# MainBoard.net
KiCad netlist of a schematic drawn in EAGLE
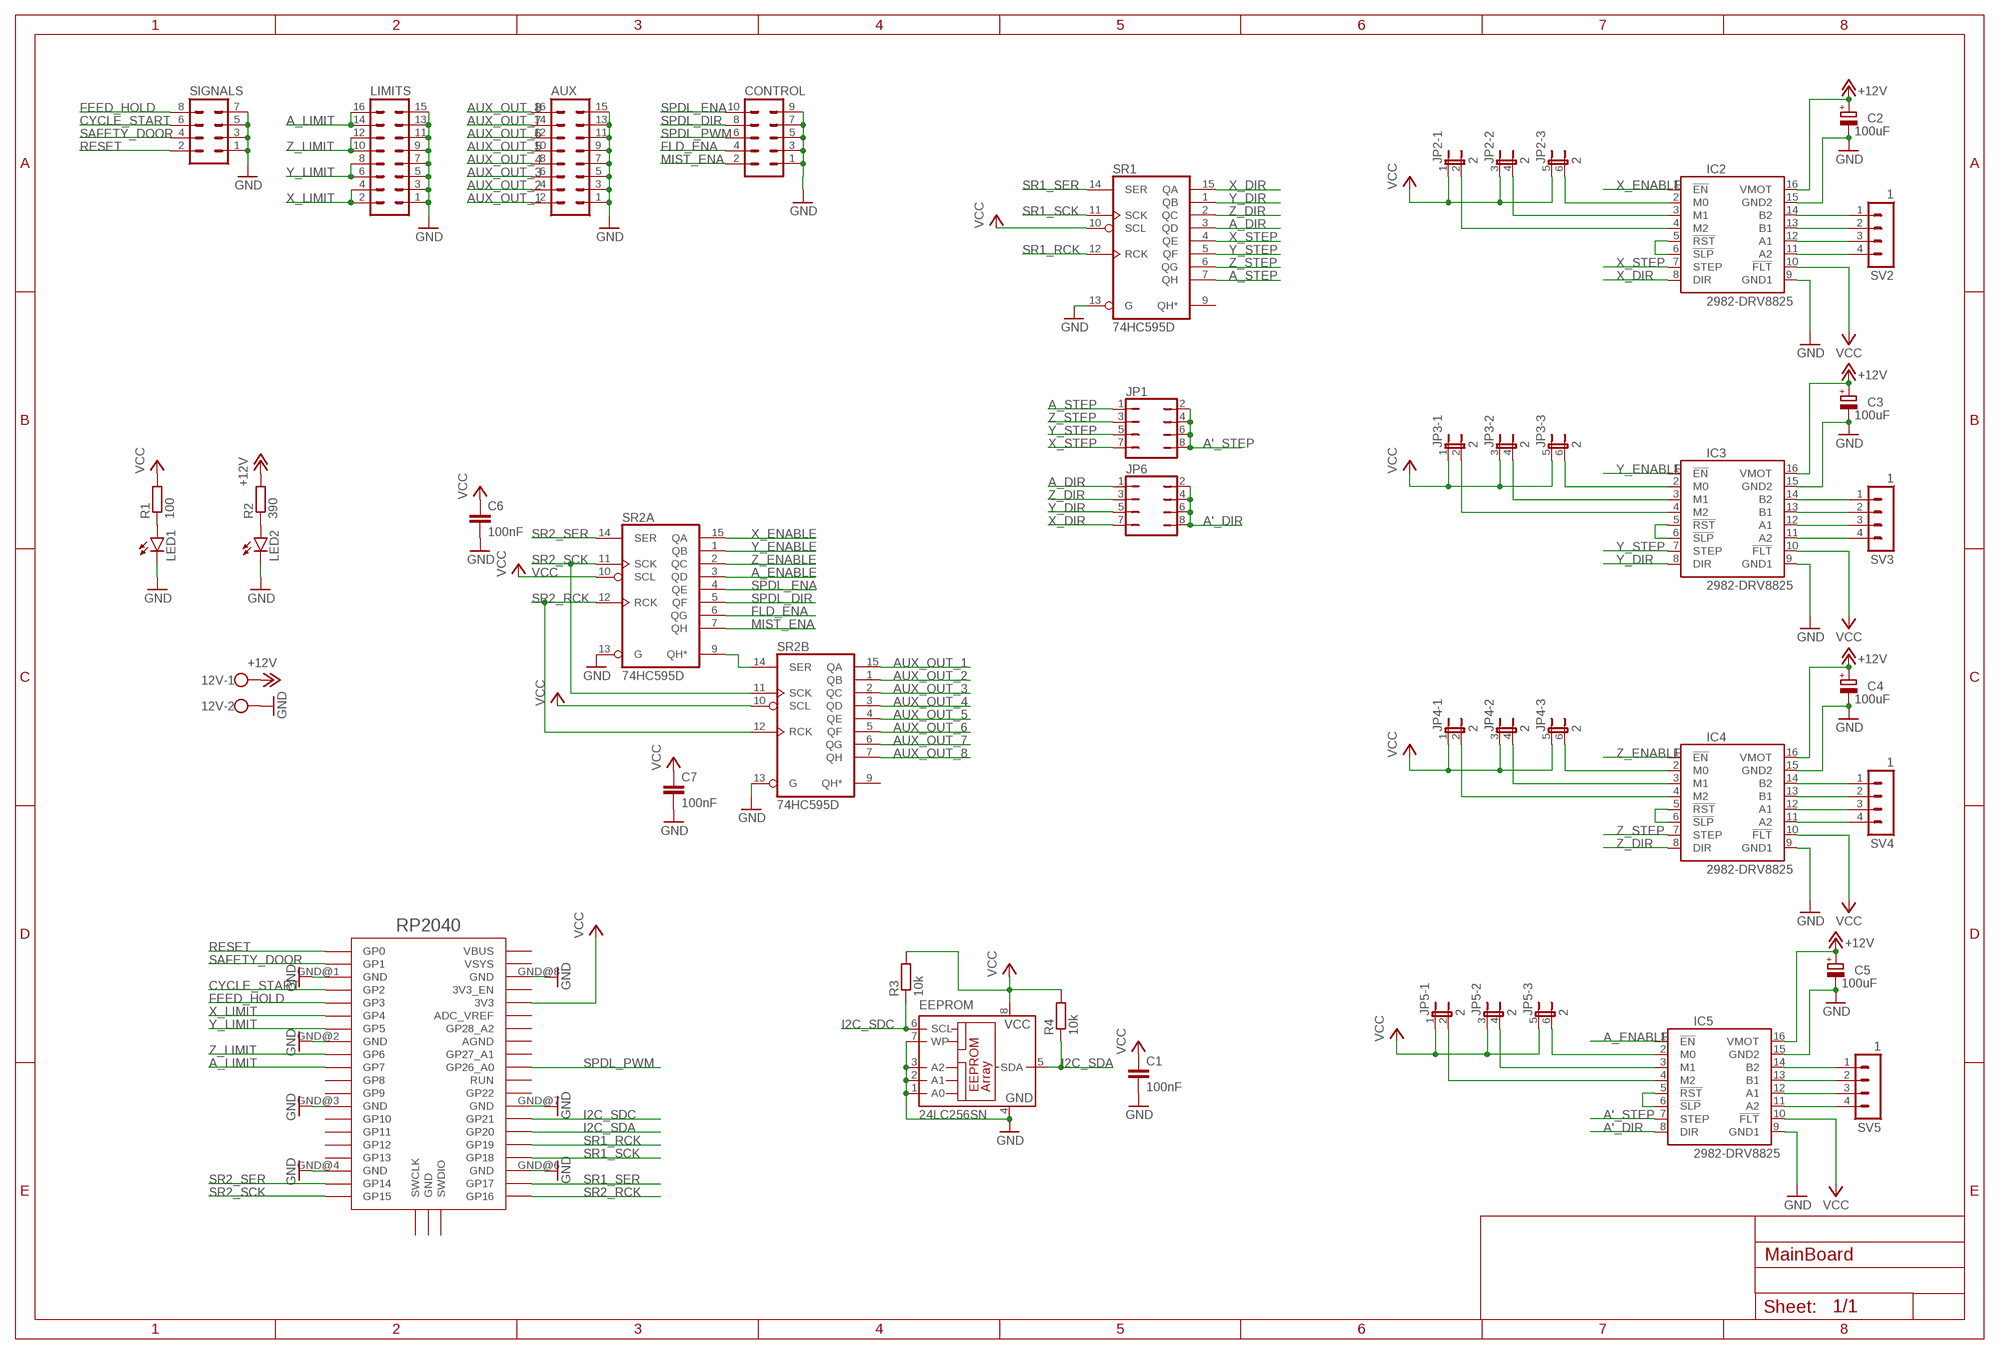
[diagram p0: schematic, sheet 1]

(export (version "E")
  (design (tool "Eeschema 10.0.6"))
  (components
    (comp (ref "12V")
      (value "W237-102")
      (footprint "eagle-import:W237-102")
      (fields (field (name "MPN") "237-102"))
      (libsource (lib "eagle-import") (part "W237-102"))
    )
    (comp (ref "AUX")
      (value "MA08-2")
      (footprint "eagle-import:MA08-2")
      (libsource (lib "eagle-import") (part "MA08-2"))
    )
    (comp (ref "C1")
      (value "100nF")
      (footprint "eagle-import:C0805")
      (libsource (lib "eagle-import") (part "C-EUC0805"))
    )
    (comp (ref "C2")
      (value "100uF")
      (footprint "eagle-import:E3,5-8")
      (libsource (lib "eagle-import") (part "CPOL-EUE3.5-8"))
    )
    (comp (ref "C3")
      (value "100uF")
      (footprint "eagle-import:E3,5-8")
      (libsource (lib "eagle-import") (part "CPOL-EUE3.5-8"))
    )
    (comp (ref "C4")
      (value "100uF")
      (footprint "eagle-import:E3,5-8")
      (libsource (lib "eagle-import") (part "CPOL-EUE3.5-8"))
    )
    (comp (ref "C5")
      (value "100uF")
      (footprint "eagle-import:E3,5-8")
      (libsource (lib "eagle-import") (part "CPOL-EUE3.5-8"))
    )
    (comp (ref "C6")
      (value "100nF")
      (footprint "eagle-import:C0805")
      (libsource (lib "eagle-import") (part "C-EUC0805"))
    )
    (comp (ref "C7")
      (value "100nF")
      (footprint "eagle-import:C0805")
      (libsource (lib "eagle-import") (part "C-EUC0805"))
    )
    (comp (ref "CONTROL")
      (value "MA05-2")
      (footprint "eagle-import:MA05-2")
      (libsource (lib "eagle-import") (part "MA05-2"))
    )
    (comp (ref "EEPROM")
      (value "24LC256SN")
      (footprint "eagle-import:SO-08")
      (fields (field (name "MF") "MICROCHIP") (field (name "MPN") "24LC256-I/SN"))
      (libsource (lib "eagle-import") (part "24SNLC256"))
    )
    (comp (ref "IC2")
      (value "2982-DRV8825")
      (footprint "eagle-import:DRV8825")
      (libsource (lib "eagle-import") (part "2982-DRV8825"))
    )
    (comp (ref "IC3")
      (value "2982-DRV8825")
      (footprint "eagle-import:DRV8825")
      (libsource (lib "eagle-import") (part "2982-DRV8825"))
    )
    (comp (ref "IC4")
      (value "2982-DRV8825")
      (footprint "eagle-import:DRV8825")
      (libsource (lib "eagle-import") (part "2982-DRV8825"))
    )
    (comp (ref "IC5")
      (value "2982-DRV8825")
      (footprint "eagle-import:DRV8825")
      (libsource (lib "eagle-import") (part "2982-DRV8825"))
    )
    (comp (ref "JP1")
      (value "JP4Q")
      (footprint "eagle-import:JP4Q")
      (libsource (lib "eagle-import") (part "JP4Q"))
    )
    (comp (ref "JP2")
      (value "2")
      (footprint "eagle-import:JP3Q")
      (libsource (lib "eagle-import") (part "JP3QE"))
    )
    (comp (ref "JP3")
      (value "2")
      (footprint "eagle-import:JP3Q")
      (libsource (lib "eagle-import") (part "JP3QE"))
    )
    (comp (ref "JP4")
      (value "2")
      (footprint "eagle-import:JP3Q")
      (libsource (lib "eagle-import") (part "JP3QE"))
    )
    (comp (ref "JP5")
      (value "2")
      (footprint "eagle-import:JP3Q")
      (libsource (lib "eagle-import") (part "JP3QE"))
    )
    (comp (ref "JP6")
      (value "JP4Q")
      (footprint "eagle-import:JP4Q")
      (libsource (lib "eagle-import") (part "JP4Q"))
    )
    (comp (ref "LED1")
      (value "LEDCHIP-LED0805")
      (footprint "eagle-import:CHIP-LED0805")
      (libsource (lib "eagle-import") (part "LEDCHIP-LED0805"))
    )
    (comp (ref "LED2")
      (value "LEDCHIP-LED0805")
      (footprint "eagle-import:CHIP-LED0805")
      (libsource (lib "eagle-import") (part "LEDCHIP-LED0805"))
    )
    (comp (ref "LIMITS")
      (value "MA08-2")
      (footprint "eagle-import:MA08-2")
      (libsource (lib "eagle-import") (part "MA08-2"))
    )
    (comp (ref "R1")
      (value "100")
      (footprint "eagle-import:R0805")
      (libsource (lib "eagle-import") (part "R-EU_R0805"))
    )
    (comp (ref "R2")
      (value "390")
      (footprint "eagle-import:R0805")
      (libsource (lib "eagle-import") (part "R-EU_R0805"))
    )
    (comp (ref "R3")
      (value "10k")
      (footprint "eagle-import:R0805")
      (libsource (lib "eagle-import") (part "R-EU_R0805"))
    )
    (comp (ref "R4")
      (value "10k")
      (footprint "eagle-import:R0805")
      (libsource (lib "eagle-import") (part "R-EU_R0805"))
    )
    (comp (ref "RP2040")
      (value "RPI_PICO_IG-TH")
      (footprint "eagle-import:RPI_PICO_TH")
      (libsource (lib "eagle-import") (part "RPI_PICO_IG-TH"))
    )
    (comp (ref "SIGNALS")
      (value "MA04-2")
      (footprint "eagle-import:MA04-2")
      (libsource (lib "eagle-import") (part "MA04-2"))
    )
    (comp (ref "SR1")
      (value "74HC595D")
      (footprint "eagle-import:SO16")
      (libsource (lib "eagle-import") (part "74595DHC"))
    )
    (comp (ref "SR2A")
      (value "74HC595D")
      (footprint "eagle-import:SO16")
      (libsource (lib "eagle-import") (part "74595DHC"))
    )
    (comp (ref "SR2B")
      (value "74HC595D")
      (footprint "eagle-import:SO16")
      (libsource (lib "eagle-import") (part "74595DHC"))
    )
    (comp (ref "SV2")
      (value "1")
      (footprint "eagle-import:MA04-1")
      (libsource (lib "eagle-import") (part "MA04-1"))
    )
    (comp (ref "SV3")
      (value "1")
      (footprint "eagle-import:MA04-1")
      (libsource (lib "eagle-import") (part "MA04-1"))
    )
    (comp (ref "SV4")
      (value "1")
      (footprint "eagle-import:MA04-1")
      (libsource (lib "eagle-import") (part "MA04-1"))
    )
    (comp (ref "SV5")
      (value "1")
      (footprint "eagle-import:MA04-1")
      (libsource (lib "eagle-import") (part "MA04-1"))
    )
  )
  (nets
    (net (code "1") (name "+12V") (class "Default")
      (node (ref "12V") (pin "1") (pinfunction "KL_1") (pintype "passive"))
      (node (ref "C2") (pin "+") (pinfunction "+_+") (pintype "passive"))
      (node (ref "C3") (pin "+") (pinfunction "+_+") (pintype "passive"))
      (node (ref "C4") (pin "+") (pinfunction "+_+") (pintype "passive"))
      (node (ref "C5") (pin "+") (pinfunction "+_+") (pintype "passive"))
      (node (ref "IC2") (pin "16") (pinfunction "VMOT_16") (pintype "power_in"))
      (node (ref "IC3") (pin "16") (pinfunction "VMOT_16") (pintype "power_in"))
      (node (ref "IC4") (pin "16") (pinfunction "VMOT_16") (pintype "power_in"))
      (node (ref "IC5") (pin "16") (pinfunction "VMOT_16") (pintype "power_in"))
      (node (ref "R2") (pin "2") (pinfunction "2_2") (pintype "passive"))
    )
    (net (code "2") (name "/A'_DIR") (class "Default")
      (node (ref "IC5") (pin "8") (pinfunction "DIR_8") (pintype "input"))
      (node (ref "JP6") (pin "2") (pinfunction "2_2") (pintype "passive"))
      (node (ref "JP6") (pin "4") (pinfunction "4_4") (pintype "passive"))
      (node (ref "JP6") (pin "6") (pinfunction "6_6") (pintype "passive"))
      (node (ref "JP6") (pin "8") (pinfunction "8_8") (pintype "passive"))
    )
    (net (code "3") (name "/A'_STEP") (class "Default")
      (node (ref "IC5") (pin "7") (pinfunction "STEP_7") (pintype "input"))
      (node (ref "JP1") (pin "2") (pinfunction "2_2") (pintype "passive"))
      (node (ref "JP1") (pin "4") (pinfunction "4_4") (pintype "passive"))
      (node (ref "JP1") (pin "6") (pinfunction "6_6") (pintype "passive"))
      (node (ref "JP1") (pin "8") (pinfunction "8_8") (pintype "passive"))
    )
    (net (code "4") (name "/AUX_OUT_1") (class "Default")
      (node (ref "AUX") (pin "2") (pinfunction "2_2") (pintype "passive"))
      (node (ref "SR2B") (pin "15") (pinfunction "QA_15") (pintype "tri_state"))
    )
    (net (code "5") (name "/AUX_OUT_2") (class "Default")
      (node (ref "AUX") (pin "4") (pinfunction "4_4") (pintype "passive"))
      (node (ref "SR2B") (pin "1") (pinfunction "QB_1") (pintype "tri_state"))
    )
    (net (code "6") (name "/AUX_OUT_3") (class "Default")
      (node (ref "AUX") (pin "6") (pinfunction "6_6") (pintype "passive"))
      (node (ref "SR2B") (pin "2") (pinfunction "QC_2") (pintype "tri_state"))
    )
    (net (code "7") (name "/AUX_OUT_4") (class "Default")
      (node (ref "AUX") (pin "8") (pinfunction "8_8") (pintype "passive"))
      (node (ref "SR2B") (pin "3") (pinfunction "QD_3") (pintype "tri_state"))
    )
    (net (code "8") (name "/AUX_OUT_5") (class "Default")
      (node (ref "AUX") (pin "10") (pinfunction "10_10") (pintype "passive"))
      (node (ref "SR2B") (pin "4") (pinfunction "QE_4") (pintype "tri_state"))
    )
    (net (code "9") (name "/AUX_OUT_6") (class "Default")
      (node (ref "AUX") (pin "12") (pinfunction "12_12") (pintype "passive"))
      (node (ref "SR2B") (pin "5") (pinfunction "QF_5") (pintype "tri_state"))
    )
    (net (code "10") (name "/AUX_OUT_7") (class "Default")
      (node (ref "AUX") (pin "14") (pinfunction "14_14") (pintype "passive"))
      (node (ref "SR2B") (pin "6") (pinfunction "QG_6") (pintype "tri_state"))
    )
    (net (code "11") (name "/AUX_OUT_8") (class "Default")
      (node (ref "AUX") (pin "16") (pinfunction "16_16") (pintype "passive"))
      (node (ref "SR2B") (pin "7") (pinfunction "QH_7") (pintype "tri_state"))
    )
    (net (code "12") (name "/A_DIR") (class "Default")
      (node (ref "JP6") (pin "1") (pinfunction "1_1") (pintype "passive"))
      (node (ref "SR1") (pin "3") (pinfunction "QD_3") (pintype "tri_state"))
    )
    (net (code "13") (name "/A_ENABLE") (class "Default")
      (node (ref "IC5") (pin "1") (pinfunction "~{EN}_1") (pintype "passive"))
      (node (ref "SR2A") (pin "3") (pinfunction "QD_3") (pintype "tri_state"))
    )
    (net (code "14") (name "/A_LIMIT") (class "Default")
      (node (ref "LIMITS") (pin "14") (pinfunction "14_14") (pintype "passive"))
      (node (ref "LIMITS") (pin "16") (pinfunction "16_16") (pintype "passive"))
      (node (ref "RP2040") (pin "GP7") (pinfunction "GP7_GP7") (pintype "bidirectional"))
    )
    (net (code "15") (name "/A_STEP") (class "Default")
      (node (ref "JP1") (pin "1") (pinfunction "1_1") (pintype "passive"))
      (node (ref "SR1") (pin "7") (pinfunction "QH_7") (pintype "tri_state"))
    )
    (net (code "16") (name "/CYCLE_START") (class "Default")
      (node (ref "RP2040") (pin "GP2") (pinfunction "GP2_GP2") (pintype "bidirectional"))
      (node (ref "SIGNALS") (pin "6") (pinfunction "6_6") (pintype "passive"))
    )
    (net (code "17") (name "/FEED_HOLD") (class "Default")
      (node (ref "RP2040") (pin "GP3") (pinfunction "GP3_GP3") (pintype "bidirectional"))
      (node (ref "SIGNALS") (pin "8") (pinfunction "8_8") (pintype "passive"))
    )
    (net (code "18") (name "/FLD_ENA") (class "Default")
      (node (ref "CONTROL") (pin "4") (pinfunction "4_4") (pintype "passive"))
      (node (ref "SR2A") (pin "6") (pinfunction "QG_6") (pintype "tri_state"))
    )
    (net (code "19") (name "/I2C_SDA") (class "Default")
      (node (ref "EEPROM") (pin "5") (pinfunction "SDA_5") (pintype "bidirectional"))
      (node (ref "R4") (pin "1") (pinfunction "1_1") (pintype "passive"))
      (node (ref "RP2040") (pin "GP20") (pinfunction "GP20_GP20") (pintype "bidirectional"))
    )
    (net (code "20") (name "/I2C_SDC") (class "Default")
      (node (ref "EEPROM") (pin "6") (pinfunction "SCL_6") (pintype "input"))
      (node (ref "R3") (pin "1") (pinfunction "1_1") (pintype "passive"))
      (node (ref "RP2040") (pin "GP21") (pinfunction "GP21_GP21") (pintype "bidirectional"))
    )
    (net (code "21") (name "/MIST_ENA") (class "Default")
      (node (ref "CONTROL") (pin "2") (pinfunction "2_2") (pintype "passive"))
      (node (ref "SR2A") (pin "7") (pinfunction "QH_7") (pintype "tri_state"))
    )
    (net (code "22") (name "/RESET") (class "Default")
      (node (ref "RP2040") (pin "GP0") (pinfunction "GP0_GP0") (pintype "bidirectional"))
      (node (ref "SIGNALS") (pin "2") (pinfunction "2_2") (pintype "passive"))
    )
    (net (code "23") (name "/SAFETY_DOOR") (class "Default")
      (node (ref "RP2040") (pin "GP1") (pinfunction "GP1_GP1") (pintype "bidirectional"))
      (node (ref "SIGNALS") (pin "4") (pinfunction "4_4") (pintype "passive"))
    )
    (net (code "24") (name "/SPDL_DIR") (class "Default")
      (node (ref "CONTROL") (pin "8") (pinfunction "8_8") (pintype "passive"))
      (node (ref "SR2A") (pin "5") (pinfunction "QF_5") (pintype "tri_state"))
    )
    (net (code "25") (name "/SPDL_ENA") (class "Default")
      (node (ref "CONTROL") (pin "10") (pinfunction "10_10") (pintype "passive"))
      (node (ref "SR2A") (pin "4") (pinfunction "QE_4") (pintype "tri_state"))
    )
    (net (code "26") (name "/SPDL_PWM") (class "Default")
      (node (ref "CONTROL") (pin "6") (pinfunction "6_6") (pintype "passive"))
      (node (ref "RP2040") (pin "GP26_A0") (pinfunction "GP26_A0_GP26_A0") (pintype "bidirectional"))
    )
    (net (code "27") (name "/SR1_RCK") (class "Default")
      (node (ref "RP2040") (pin "GP19") (pinfunction "GP19_GP19") (pintype "bidirectional"))
      (node (ref "SR1") (pin "12") (pinfunction "RCK_12") (pintype "input"))
    )
    (net (code "28") (name "/SR1_SCK") (class "Default")
      (node (ref "RP2040") (pin "GP18") (pinfunction "GP18_GP18") (pintype "bidirectional"))
      (node (ref "SR1") (pin "11") (pinfunction "SCK_11") (pintype "input"))
    )
    (net (code "29") (name "/SR1_SER") (class "Default")
      (node (ref "RP2040") (pin "GP17") (pinfunction "GP17_GP17") (pintype "bidirectional"))
      (node (ref "SR1") (pin "14") (pinfunction "SER_14") (pintype "input"))
    )
    (net (code "30") (name "/SR2_RCK") (class "Default")
      (node (ref "RP2040") (pin "GP16") (pinfunction "GP16_GP16") (pintype "bidirectional"))
      (node (ref "SR2A") (pin "12") (pinfunction "RCK_12") (pintype "input"))
      (node (ref "SR2B") (pin "12") (pinfunction "RCK_12") (pintype "input"))
    )
    (net (code "31") (name "/SR2_SCK") (class "Default")
      (node (ref "RP2040") (pin "GP15") (pinfunction "GP15_GP15") (pintype "bidirectional"))
      (node (ref "SR2A") (pin "11") (pinfunction "SCK_11") (pintype "input"))
      (node (ref "SR2B") (pin "11") (pinfunction "SCK_11") (pintype "input"))
    )
    (net (code "32") (name "/SR2_SER") (class "Default")
      (node (ref "RP2040") (pin "GP14") (pinfunction "GP14_GP14") (pintype "bidirectional"))
      (node (ref "SR2A") (pin "14") (pinfunction "SER_14") (pintype "input"))
    )
    (net (code "33") (name "/X_DIR") (class "Default")
      (node (ref "IC2") (pin "8") (pinfunction "DIR_8") (pintype "input"))
      (node (ref "JP6") (pin "7") (pinfunction "7_7") (pintype "passive"))
      (node (ref "SR1") (pin "15") (pinfunction "QA_15") (pintype "tri_state"))
    )
    (net (code "34") (name "/X_ENABLE") (class "Default")
      (node (ref "IC2") (pin "1") (pinfunction "~{EN}_1") (pintype "passive"))
      (node (ref "SR2A") (pin "15") (pinfunction "QA_15") (pintype "tri_state"))
    )
    (net (code "35") (name "/X_LIMIT") (class "Default")
      (node (ref "LIMITS") (pin "2") (pinfunction "2_2") (pintype "passive"))
      (node (ref "LIMITS") (pin "4") (pinfunction "4_4") (pintype "passive"))
      (node (ref "RP2040") (pin "GP4") (pinfunction "GP4_GP4") (pintype "bidirectional"))
    )
    (net (code "36") (name "/X_STEP") (class "Default")
      (node (ref "IC2") (pin "7") (pinfunction "STEP_7") (pintype "input"))
      (node (ref "JP1") (pin "7") (pinfunction "7_7") (pintype "passive"))
      (node (ref "SR1") (pin "4") (pinfunction "QE_4") (pintype "tri_state"))
    )
    (net (code "37") (name "/Y_DIR") (class "Default")
      (node (ref "IC3") (pin "8") (pinfunction "DIR_8") (pintype "input"))
      (node (ref "JP6") (pin "5") (pinfunction "5_5") (pintype "passive"))
      (node (ref "SR1") (pin "1") (pinfunction "QB_1") (pintype "tri_state"))
    )
    (net (code "38") (name "/Y_ENABLE") (class "Default")
      (node (ref "IC3") (pin "1") (pinfunction "~{EN}_1") (pintype "passive"))
      (node (ref "SR2A") (pin "1") (pinfunction "QB_1") (pintype "tri_state"))
    )
    (net (code "39") (name "/Y_LIMIT") (class "Default")
      (node (ref "LIMITS") (pin "6") (pinfunction "6_6") (pintype "passive"))
      (node (ref "LIMITS") (pin "8") (pinfunction "8_8") (pintype "passive"))
      (node (ref "RP2040") (pin "GP5") (pinfunction "GP5_GP5") (pintype "bidirectional"))
    )
    (net (code "40") (name "/Y_STEP") (class "Default")
      (node (ref "IC3") (pin "7") (pinfunction "STEP_7") (pintype "input"))
      (node (ref "JP1") (pin "5") (pinfunction "5_5") (pintype "passive"))
      (node (ref "SR1") (pin "5") (pinfunction "QF_5") (pintype "tri_state"))
    )
    (net (code "41") (name "/Z_DIR") (class "Default")
      (node (ref "IC4") (pin "8") (pinfunction "DIR_8") (pintype "input"))
      (node (ref "JP6") (pin "3") (pinfunction "3_3") (pintype "passive"))
      (node (ref "SR1") (pin "2") (pinfunction "QC_2") (pintype "tri_state"))
    )
    (net (code "42") (name "/Z_ENABLE") (class "Default")
      (node (ref "IC4") (pin "1") (pinfunction "~{EN}_1") (pintype "passive"))
      (node (ref "SR2A") (pin "2") (pinfunction "QC_2") (pintype "tri_state"))
    )
    (net (code "43") (name "/Z_LIMIT") (class "Default")
      (node (ref "LIMITS") (pin "10") (pinfunction "10_10") (pintype "passive"))
      (node (ref "LIMITS") (pin "12") (pinfunction "12_12") (pintype "passive"))
      (node (ref "RP2040") (pin "GP6") (pinfunction "GP6_GP6") (pintype "bidirectional"))
    )
    (net (code "44") (name "/Z_STEP") (class "Default")
      (node (ref "IC4") (pin "7") (pinfunction "STEP_7") (pintype "input"))
      (node (ref "JP1") (pin "3") (pinfunction "3_3") (pintype "passive"))
      (node (ref "SR1") (pin "6") (pinfunction "QG_6") (pintype "tri_state"))
    )
    (net (code "45") (name "GND") (class "Default")
      (node (ref "12V") (pin "2") (pinfunction "KL_2") (pintype "passive"))
      (node (ref "AUX") (pin "1") (pinfunction "1_1") (pintype "passive"))
      (node (ref "AUX") (pin "11") (pinfunction "11_11") (pintype "passive"))
      (node (ref "AUX") (pin "13") (pinfunction "13_13") (pintype "passive"))
      (node (ref "AUX") (pin "15") (pinfunction "15_15") (pintype "passive"))
      (node (ref "AUX") (pin "3") (pinfunction "3_3") (pintype "passive"))
      (node (ref "AUX") (pin "5") (pinfunction "5_5") (pintype "passive"))
      (node (ref "AUX") (pin "7") (pinfunction "7_7") (pintype "passive"))
      (node (ref "AUX") (pin "9") (pinfunction "9_9") (pintype "passive"))
      (node (ref "C1") (pin "2") (pinfunction "2_2") (pintype "passive"))
      (node (ref "C2") (pin "-") (pinfunction "-_-") (pintype "passive"))
      (node (ref "C3") (pin "-") (pinfunction "-_-") (pintype "passive"))
      (node (ref "C4") (pin "-") (pinfunction "-_-") (pintype "passive"))
      (node (ref "C5") (pin "-") (pinfunction "-_-") (pintype "passive"))
      (node (ref "C6") (pin "2") (pinfunction "2_2") (pintype "passive"))
      (node (ref "C7") (pin "2") (pinfunction "2_2") (pintype "passive"))
      (node (ref "CONTROL") (pin "1") (pinfunction "1_1") (pintype "passive"))
      (node (ref "CONTROL") (pin "3") (pinfunction "3_3") (pintype "passive"))
      (node (ref "CONTROL") (pin "5") (pinfunction "5_5") (pintype "passive"))
      (node (ref "CONTROL") (pin "7") (pinfunction "7_7") (pintype "passive"))
      (node (ref "CONTROL") (pin "9") (pinfunction "9_9") (pintype "passive"))
      (node (ref "EEPROM") (pin "1") (pinfunction "A0_1") (pintype "input"))
      (node (ref "EEPROM") (pin "2") (pinfunction "A1_2") (pintype "input"))
      (node (ref "EEPROM") (pin "3") (pinfunction "A2_3") (pintype "input"))
      (node (ref "EEPROM") (pin "4") (pinfunction "GND_4") (pintype "power_in"))
      (node (ref "EEPROM") (pin "7") (pinfunction "WP_7") (pintype "input"))
      (node (ref "IC2") (pin "15") (pinfunction "GND2_15") (pintype "power_in"))
      (node (ref "IC2") (pin "9") (pinfunction "GND1_9") (pintype "power_in"))
      (node (ref "IC3") (pin "15") (pinfunction "GND2_15") (pintype "power_in"))
      (node (ref "IC3") (pin "9") (pinfunction "GND1_9") (pintype "power_in"))
      (node (ref "IC4") (pin "15") (pinfunction "GND2_15") (pintype "power_in"))
      (node (ref "IC4") (pin "9") (pinfunction "GND1_9") (pintype "power_in"))
      (node (ref "IC5") (pin "15") (pinfunction "GND2_15") (pintype "power_in"))
      (node (ref "IC5") (pin "9") (pinfunction "GND1_9") (pintype "power_in"))
      (node (ref "LED1") (pin "C") (pinfunction "C_C") (pintype "passive"))
      (node (ref "LED2") (pin "C") (pinfunction "C_C") (pintype "passive"))
      (node (ref "LIMITS") (pin "1") (pinfunction "1_1") (pintype "passive"))
      (node (ref "LIMITS") (pin "11") (pinfunction "11_11") (pintype "passive"))
      (node (ref "LIMITS") (pin "13") (pinfunction "13_13") (pintype "passive"))
      (node (ref "LIMITS") (pin "15") (pinfunction "15_15") (pintype "passive"))
      (node (ref "LIMITS") (pin "3") (pinfunction "3_3") (pintype "passive"))
      (node (ref "LIMITS") (pin "5") (pinfunction "5_5") (pintype "passive"))
      (node (ref "LIMITS") (pin "7") (pinfunction "7_7") (pintype "passive"))
      (node (ref "LIMITS") (pin "9") (pinfunction "9_9") (pintype "passive"))
      (node (ref "RP2040") (pin "GND@1") (pinfunction "GND_GND@1") (pintype "bidirectional"))
      (node (ref "RP2040") (pin "GND@2") (pinfunction "GND_GND@2") (pintype "bidirectional"))
      (node (ref "RP2040") (pin "GND@3") (pinfunction "GND_GND@3") (pintype "bidirectional"))
      (node (ref "RP2040") (pin "GND@4") (pinfunction "GND_GND@4") (pintype "bidirectional"))
      (node (ref "RP2040") (pin "GND@6") (pinfunction "GND_GND@6") (pintype "bidirectional"))
      (node (ref "RP2040") (pin "GND@7") (pinfunction "GND_GND@7") (pintype "bidirectional"))
      (node (ref "RP2040") (pin "GND@8") (pinfunction "GND_GND@8") (pintype "bidirectional"))
      (node (ref "SIGNALS") (pin "1") (pinfunction "1_1") (pintype "passive"))
      (node (ref "SIGNALS") (pin "3") (pinfunction "3_3") (pintype "passive"))
      (node (ref "SIGNALS") (pin "5") (pinfunction "5_5") (pintype "passive"))
      (node (ref "SIGNALS") (pin "7") (pinfunction "7_7") (pintype "passive"))
      (node (ref "SR1") (pin "13") (pinfunction "G_13") (pintype "input"))
      (node (ref "SR2A") (pin "13") (pinfunction "G_13") (pintype "input"))
      (node (ref "SR2B") (pin "13") (pinfunction "G_13") (pintype "input"))
    )
    (net (code "46") (name "Net-(IC2-A1)") (class "Default")
      (node (ref "IC2") (pin "12") (pinfunction "A1_12") (pintype "output"))
      (node (ref "SV2") (pin "3") (pinfunction "3_3") (pintype "passive"))
    )
    (net (code "47") (name "Net-(IC2-A2)") (class "Default")
      (node (ref "IC2") (pin "11") (pinfunction "A2_11") (pintype "output"))
      (node (ref "SV2") (pin "4") (pinfunction "4_4") (pintype "passive"))
    )
    (net (code "48") (name "Net-(IC2-B1)") (class "Default")
      (node (ref "IC2") (pin "13") (pinfunction "B1_13") (pintype "output"))
      (node (ref "SV2") (pin "2") (pinfunction "2_2") (pintype "passive"))
    )
    (net (code "49") (name "Net-(IC2-B2)") (class "Default")
      (node (ref "IC2") (pin "14") (pinfunction "B2_14") (pintype "output"))
      (node (ref "SV2") (pin "1") (pinfunction "1_1") (pintype "passive"))
    )
    (net (code "50") (name "Net-(IC2-M0)") (class "Default")
      (node (ref "IC2") (pin "2") (pinfunction "M0_2") (pintype "passive"))
      (node (ref "JP2") (pin "6") (pinfunction "2_6") (pintype "passive"))
    )
    (net (code "51") (name "Net-(IC2-M1)") (class "Default")
      (node (ref "IC2") (pin "3") (pinfunction "M1_3") (pintype "passive"))
      (node (ref "JP2") (pin "4") (pinfunction "2_4") (pintype "passive"))
    )
    (net (code "52") (name "Net-(IC2-M2)") (class "Default")
      (node (ref "IC2") (pin "4") (pinfunction "M2_4") (pintype "passive"))
      (node (ref "JP2") (pin "2") (pinfunction "2_2") (pintype "passive"))
    )
    (net (code "53") (name "Net-(IC2-~{RST})") (class "Default")
      (node (ref "IC2") (pin "5") (pinfunction "~{RST}_5") (pintype "input"))
      (node (ref "IC2") (pin "6") (pinfunction "~{SLP}_6") (pintype "input"))
    )
    (net (code "54") (name "Net-(IC3-A1)") (class "Default")
      (node (ref "IC3") (pin "12") (pinfunction "A1_12") (pintype "output"))
      (node (ref "SV3") (pin "3") (pinfunction "3_3") (pintype "passive"))
    )
    (net (code "55") (name "Net-(IC3-A2)") (class "Default")
      (node (ref "IC3") (pin "11") (pinfunction "A2_11") (pintype "output"))
      (node (ref "SV3") (pin "4") (pinfunction "4_4") (pintype "passive"))
    )
    (net (code "56") (name "Net-(IC3-B1)") (class "Default")
      (node (ref "IC3") (pin "13") (pinfunction "B1_13") (pintype "output"))
      (node (ref "SV3") (pin "2") (pinfunction "2_2") (pintype "passive"))
    )
    (net (code "57") (name "Net-(IC3-B2)") (class "Default")
      (node (ref "IC3") (pin "14") (pinfunction "B2_14") (pintype "output"))
      (node (ref "SV3") (pin "1") (pinfunction "1_1") (pintype "passive"))
    )
    (net (code "58") (name "Net-(IC3-M0)") (class "Default")
      (node (ref "IC3") (pin "2") (pinfunction "M0_2") (pintype "passive"))
      (node (ref "JP3") (pin "6") (pinfunction "2_6") (pintype "passive"))
    )
    (net (code "59") (name "Net-(IC3-M1)") (class "Default")
      (node (ref "IC3") (pin "3") (pinfunction "M1_3") (pintype "passive"))
      (node (ref "JP3") (pin "4") (pinfunction "2_4") (pintype "passive"))
    )
    (net (code "60") (name "Net-(IC3-M2)") (class "Default")
      (node (ref "IC3") (pin "4") (pinfunction "M2_4") (pintype "passive"))
      (node (ref "JP3") (pin "2") (pinfunction "2_2") (pintype "passive"))
    )
    (net (code "61") (name "Net-(IC3-~{RST})") (class "Default")
      (node (ref "IC3") (pin "5") (pinfunction "~{RST}_5") (pintype "input"))
      (node (ref "IC3") (pin "6") (pinfunction "~{SLP}_6") (pintype "input"))
    )
    (net (code "62") (name "Net-(IC4-A1)") (class "Default")
      (node (ref "IC4") (pin "12") (pinfunction "A1_12") (pintype "output"))
      (node (ref "SV4") (pin "3") (pinfunction "3_3") (pintype "passive"))
    )
    (net (code "63") (name "Net-(IC4-A2)") (class "Default")
      (node (ref "IC4") (pin "11") (pinfunction "A2_11") (pintype "output"))
      (node (ref "SV4") (pin "4") (pinfunction "4_4") (pintype "passive"))
    )
    (net (code "64") (name "Net-(IC4-B1)") (class "Default")
      (node (ref "IC4") (pin "13") (pinfunction "B1_13") (pintype "output"))
      (node (ref "SV4") (pin "2") (pinfunction "2_2") (pintype "passive"))
    )
    (net (code "65") (name "Net-(IC4-B2)") (class "Default")
      (node (ref "IC4") (pin "14") (pinfunction "B2_14") (pintype "output"))
      (node (ref "SV4") (pin "1") (pinfunction "1_1") (pintype "passive"))
    )
    (net (code "66") (name "Net-(IC4-M0)") (class "Default")
      (node (ref "IC4") (pin "2") (pinfunction "M0_2") (pintype "passive"))
      (node (ref "JP4") (pin "6") (pinfunction "2_6") (pintype "passive"))
    )
    (net (code "67") (name "Net-(IC4-M1)") (class "Default")
      (node (ref "IC4") (pin "3") (pinfunction "M1_3") (pintype "passive"))
      (node (ref "JP4") (pin "4") (pinfunction "2_4") (pintype "passive"))
    )
    (net (code "68") (name "Net-(IC4-M2)") (class "Default")
      (node (ref "IC4") (pin "4") (pinfunction "M2_4") (pintype "passive"))
      (node (ref "JP4") (pin "2") (pinfunction "2_2") (pintype "passive"))
    )
    (net (code "69") (name "Net-(IC4-~{RST})") (class "Default")
      (node (ref "IC4") (pin "5") (pinfunction "~{RST}_5") (pintype "input"))
      (node (ref "IC4") (pin "6") (pinfunction "~{SLP}_6") (pintype "input"))
    )
    (net (code "70") (name "Net-(IC5-A1)") (class "Default")
      (node (ref "IC5") (pin "12") (pinfunction "A1_12") (pintype "output"))
      (node (ref "SV5") (pin "3") (pinfunction "3_3") (pintype "passive"))
    )
    (net (code "71") (name "Net-(IC5-A2)") (class "Default")
      (node (ref "IC5") (pin "11") (pinfunction "A2_11") (pintype "output"))
      (node (ref "SV5") (pin "4") (pinfunction "4_4") (pintype "passive"))
    )
    (net (code "72") (name "Net-(IC5-B1)") (class "Default")
      (node (ref "IC5") (pin "13") (pinfunction "B1_13") (pintype "output"))
      (node (ref "SV5") (pin "2") (pinfunction "2_2") (pintype "passive"))
    )
    (net (code "73") (name "Net-(IC5-B2)") (class "Default")
      (node (ref "IC5") (pin "14") (pinfunction "B2_14") (pintype "output"))
      (node (ref "SV5") (pin "1") (pinfunction "1_1") (pintype "passive"))
    )
    (net (code "74") (name "Net-(IC5-M0)") (class "Default")
      (node (ref "IC5") (pin "2") (pinfunction "M0_2") (pintype "passive"))
      (node (ref "JP5") (pin "6") (pinfunction "2_6") (pintype "passive"))
    )
    (net (code "75") (name "Net-(IC5-M1)") (class "Default")
      (node (ref "IC5") (pin "3") (pinfunction "M1_3") (pintype "passive"))
      (node (ref "JP5") (pin "4") (pinfunction "2_4") (pintype "passive"))
    )
    (net (code "76") (name "Net-(IC5-M2)") (class "Default")
      (node (ref "IC5") (pin "4") (pinfunction "M2_4") (pintype "passive"))
      (node (ref "JP5") (pin "2") (pinfunction "2_2") (pintype "passive"))
    )
    (net (code "77") (name "Net-(IC5-~{RST})") (class "Default")
      (node (ref "IC5") (pin "5") (pinfunction "~{RST}_5") (pintype "input"))
      (node (ref "IC5") (pin "6") (pinfunction "~{SLP}_6") (pintype "input"))
    )
    (net (code "78") (name "Net-(LED1-PadA)") (class "Default")
      (node (ref "LED1") (pin "A") (pinfunction "A_A") (pintype "passive"))
      (node (ref "R1") (pin "1") (pinfunction "1_1") (pintype "passive"))
    )
    (net (code "79") (name "Net-(LED2-PadA)") (class "Default")
      (node (ref "LED2") (pin "A") (pinfunction "A_A") (pintype "passive"))
      (node (ref "R2") (pin "1") (pinfunction "1_1") (pintype "passive"))
    )
    (net (code "80") (name "Net-(SR2AA-QH*)") (class "Default")
      (node (ref "SR2A") (pin "9") (pinfunction "QH*_9") (pintype "tri_state"))
      (node (ref "SR2B") (pin "14") (pinfunction "SER_14") (pintype "input"))
    )
    (net (code "81") (name "VCC") (class "Default")
      (node (ref "C1") (pin "1") (pinfunction "1_1") (pintype "passive"))
      (node (ref "C6") (pin "1") (pinfunction "1_1") (pintype "passive"))
      (node (ref "C7") (pin "1") (pinfunction "1_1") (pintype "passive"))
      (node (ref "EEPROM") (pin "8") (pinfunction "VCC_8") (pintype "power_in"))
      (node (ref "IC2") (pin "10") (pinfunction "~{FLT}_10") (pintype "open_collector"))
      (node (ref "IC3") (pin "10") (pinfunction "~{FLT}_10") (pintype "open_collector"))
      (node (ref "IC4") (pin "10") (pinfunction "~{FLT}_10") (pintype "open_collector"))
      (node (ref "IC5") (pin "10") (pinfunction "~{FLT}_10") (pintype "open_collector"))
      (node (ref "JP2") (pin "1") (pinfunction "1_1") (pintype "passive"))
      (node (ref "JP2") (pin "3") (pinfunction "1_3") (pintype "passive"))
      (node (ref "JP2") (pin "5") (pinfunction "1_5") (pintype "passive"))
      (node (ref "JP3") (pin "1") (pinfunction "1_1") (pintype "passive"))
      (node (ref "JP3") (pin "3") (pinfunction "1_3") (pintype "passive"))
      (node (ref "JP3") (pin "5") (pinfunction "1_5") (pintype "passive"))
      (node (ref "JP4") (pin "1") (pinfunction "1_1") (pintype "passive"))
      (node (ref "JP4") (pin "3") (pinfunction "1_3") (pintype "passive"))
      (node (ref "JP4") (pin "5") (pinfunction "1_5") (pintype "passive"))
      (node (ref "JP5") (pin "1") (pinfunction "1_1") (pintype "passive"))
      (node (ref "JP5") (pin "3") (pinfunction "1_3") (pintype "passive"))
      (node (ref "JP5") (pin "5") (pinfunction "1_5") (pintype "passive"))
      (node (ref "R1") (pin "2") (pinfunction "2_2") (pintype "passive"))
      (node (ref "R3") (pin "2") (pinfunction "2_2") (pintype "passive"))
      (node (ref "R4") (pin "2") (pinfunction "2_2") (pintype "passive"))
      (node (ref "RP2040") (pin "3V3") (pinfunction "3V3_3V3") (pintype "bidirectional"))
      (node (ref "SR1") (pin "10") (pinfunction "SCL_10") (pintype "input"))
      (node (ref "SR2A") (pin "10") (pinfunction "SCL_10") (pintype "input"))
      (node (ref "SR2B") (pin "10") (pinfunction "SCL_10") (pintype "input"))
    )
    (net (code "82") (name "unconnected-(RP2040-GND-PadGND@5)") (class "Default")
      (node (ref "RP2040") (pin "GND@5") (pinfunction "GND_GND@5") (pintype "bidirectional"))
    )
    (net (code "83") (name "unconnected-(RP2040-Pad3V3_EN)") (class "Default")
      (node (ref "RP2040") (pin "3V3_EN") (pinfunction "3V3_EN_3V3_EN") (pintype "bidirectional"))
    )
    (net (code "84") (name "unconnected-(RP2040-PadADC_VREF)") (class "Default")
      (node (ref "RP2040") (pin "ADC_VREF") (pinfunction "ADC_VREF_ADC_VREF") (pintype "bidirectional"))
    )
    (net (code "85") (name "unconnected-(RP2040-PadAGND)") (class "Default")
      (node (ref "RP2040") (pin "AGND") (pinfunction "AGND_AGND") (pintype "bidirectional"))
    )
    (net (code "86") (name "unconnected-(RP2040-PadGP8)") (class "Default")
      (node (ref "RP2040") (pin "GP8") (pinfunction "GP8_GP8") (pintype "bidirectional"))
    )
    (net (code "87") (name "unconnected-(RP2040-PadGP9)") (class "Default")
      (node (ref "RP2040") (pin "GP9") (pinfunction "GP9_GP9") (pintype "bidirectional"))
    )
    (net (code "88") (name "unconnected-(RP2040-PadGP10)") (class "Default")
      (node (ref "RP2040") (pin "GP10") (pinfunction "GP10_GP10") (pintype "bidirectional"))
    )
    (net (code "89") (name "unconnected-(RP2040-PadGP11)") (class "Default")
      (node (ref "RP2040") (pin "GP11") (pinfunction "GP11_GP11") (pintype "bidirectional"))
    )
    (net (code "90") (name "unconnected-(RP2040-PadGP12)") (class "Default")
      (node (ref "RP2040") (pin "GP12") (pinfunction "GP12_GP12") (pintype "bidirectional"))
    )
    (net (code "91") (name "unconnected-(RP2040-PadGP13)") (class "Default")
      (node (ref "RP2040") (pin "GP13") (pinfunction "GP13_GP13") (pintype "bidirectional"))
    )
    (net (code "92") (name "unconnected-(RP2040-PadGP22)") (class "Default")
      (node (ref "RP2040") (pin "GP22") (pinfunction "GP22_GP22") (pintype "bidirectional"))
    )
    (net (code "93") (name "unconnected-(RP2040-PadGP27_A1)") (class "Default")
      (node (ref "RP2040") (pin "GP27_A1") (pinfunction "GP27_A1_GP27_A1") (pintype "bidirectional"))
    )
    (net (code "94") (name "unconnected-(RP2040-PadGP28_A2)") (class "Default")
      (node (ref "RP2040") (pin "GP28_A2") (pinfunction "GP28_A2_GP28_A2") (pintype "bidirectional"))
    )
    (net (code "95") (name "unconnected-(RP2040-PadRUN)") (class "Default")
      (node (ref "RP2040") (pin "RUN") (pinfunction "RUN_RUN") (pintype "bidirectional"))
    )
    (net (code "96") (name "unconnected-(RP2040-PadSWCLK)") (class "Default")
      (node (ref "RP2040") (pin "SWCLK") (pinfunction "SWCLK_SWCLK") (pintype "bidirectional"))
    )
    (net (code "97") (name "unconnected-(RP2040-PadSWDIO)") (class "Default")
      (node (ref "RP2040") (pin "SWDIO") (pinfunction "SWDIO_SWDIO") (pintype "bidirectional"))
    )
    (net (code "98") (name "unconnected-(RP2040-PadVBUS)") (class "Default")
      (node (ref "RP2040") (pin "VBUS") (pinfunction "VBUS_VBUS") (pintype "bidirectional"))
    )
    (net (code "99") (name "unconnected-(RP2040-PadVSYS)") (class "Default")
      (node (ref "RP2040") (pin "VSYS") (pinfunction "VSYS_VSYS") (pintype "bidirectional"))
    )
    (net (code "100") (name "unconnected-(SR1A-QH*-Pad9)") (class "Default")
      (node (ref "SR1") (pin "9") (pinfunction "QH*_9") (pintype "tri_state"))
    )
    (net (code "101") (name "unconnected-(SR2BA-QH*-Pad9)") (class "Default")
      (node (ref "SR2B") (pin "9") (pinfunction "QH*_9") (pintype "tri_state"))
    )
  )
)
